# StageAudioPlayer.net
KiCad netlist of a schematic drawn in EasyEDA Pro
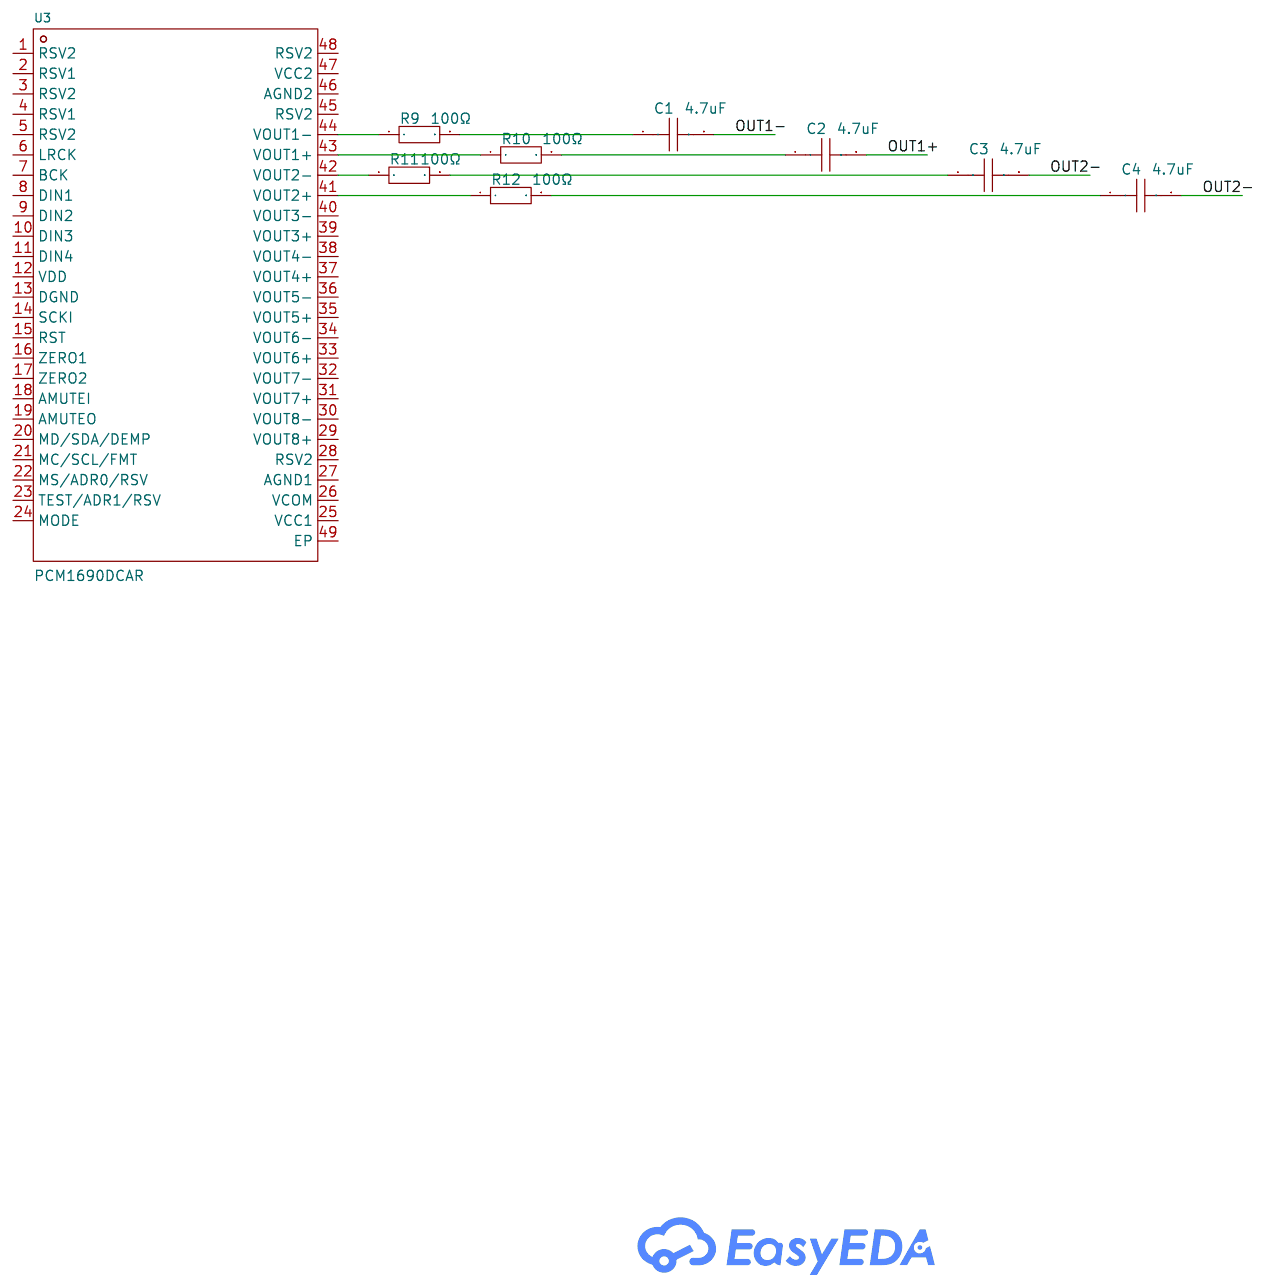
[diagram p0: schematic sheet]

(export (version "E")
  (design (tool "Eeschema 10.0.6"))
  (components
    (comp (ref "C1")
      (value "4.7uF")
      (footprint "easyedapro:CAP-TH_L28.5-W15.5-P26.0-D0.8")
      (fields (field (name "Manufacturer Part") "KP475J2J2603") (field (name "Manufacturer") "KYET(科雅)"))
      (libsource (lib "easyedapro") (part "KP475J2J2603"))
    )
    (comp (ref "C2")
      (value "4.7uF")
      (footprint "easyedapro:CAP-TH_L28.5-W15.5-P26.0-D0.8")
      (fields (field (name "Manufacturer Part") "KP475J2J2603") (field (name "Manufacturer") "KYET(科雅)"))
      (libsource (lib "easyedapro") (part "KP475J2J2603"))
    )
    (comp (ref "C3")
      (value "4.7uF")
      (footprint "easyedapro:CAP-TH_L28.5-W15.5-P26.0-D0.8")
      (fields (field (name "Manufacturer Part") "KP475J2J2603") (field (name "Manufacturer") "KYET(科雅)"))
      (libsource (lib "easyedapro") (part "KP475J2J2603"))
    )
    (comp (ref "C4")
      (value "4.7uF")
      (footprint "easyedapro:CAP-TH_L28.5-W15.5-P26.0-D0.8")
      (fields (field (name "Manufacturer Part") "KP475J2J2603") (field (name "Manufacturer") "KYET(科雅)"))
      (libsource (lib "easyedapro") (part "KP475J2J2603"))
    )
    (comp (ref "R9")
      (value "100Ω")
      (footprint "easyedapro:R0603")
      (fields
        (field (name "Manufacturer Part") "0603WAF1000T5E")
        (field (name "Manufacturer") "UNI-ROYAL(厚声)")
      )
      (libsource (lib "easyedapro") (part "0603WAF1000T5E"))
    )
    (comp (ref "R10")
      (value "100Ω")
      (footprint "easyedapro:R0603")
      (fields
        (field (name "Manufacturer Part") "0603WAF1000T5E")
        (field (name "Manufacturer") "UNI-ROYAL(厚声)")
      )
      (libsource (lib "easyedapro") (part "0603WAF1000T5E"))
    )
    (comp (ref "R11")
      (value "100Ω")
      (footprint "easyedapro:R0603")
      (fields
        (field (name "Manufacturer Part") "0603WAF1000T5E")
        (field (name "Manufacturer") "UNI-ROYAL(厚声)")
      )
      (libsource (lib "easyedapro") (part "0603WAF1000T5E"))
    )
    (comp (ref "R12")
      (value "100Ω")
      (footprint "easyedapro:R0603")
      (fields
        (field (name "Manufacturer Part") "0603WAF1000T5E")
        (field (name "Manufacturer") "UNI-ROYAL(厚声)")
      )
      (libsource (lib "easyedapro") (part "0603WAF1000T5E"))
    )
    (comp (ref "U3")
      (value "PCM1690DCAR")
      (footprint "easyedapro:HTSSOP-48_L12.5-W6.1-P0.50-LS8.1-BL-EP-1")
      (fields (field (name "Manufacturer") "TI(德州仪器)"))
      (libsource (lib "easyedapro") (part "PCM1690DCAR"))
    )
  )
  (nets
    (net (code "1") (name "/OUT1+") (class "Default")
      (node (ref "C2") (pin "2") (pinfunction "2_2") (pintype "unspecified"))
    )
    (net (code "2") (name "/OUT1-") (class "Default")
      (node (ref "C1") (pin "2") (pinfunction "2_2") (pintype "unspecified"))
    )
    (net (code "3") (name "/OUT2-") (class "Default")
      (node (ref "C3") (pin "2") (pinfunction "2_2") (pintype "unspecified"))
      (node (ref "C4") (pin "2") (pinfunction "2_2") (pintype "unspecified"))
    )
    (net (code "4") (name "Net-(C1-Pad1)") (class "Default")
      (node (ref "C1") (pin "1") (pinfunction "1_1") (pintype "unspecified"))
      (node (ref "R9") (pin "2") (pinfunction "2_2") (pintype "input"))
    )
    (net (code "5") (name "Net-(C2-Pad1)") (class "Default")
      (node (ref "C2") (pin "1") (pinfunction "1_1") (pintype "unspecified"))
      (node (ref "R10") (pin "2") (pinfunction "2_2") (pintype "input"))
    )
    (net (code "6") (name "Net-(C3-Pad1)") (class "Default")
      (node (ref "C3") (pin "1") (pinfunction "1_1") (pintype "unspecified"))
      (node (ref "R11") (pin "2") (pinfunction "2_2") (pintype "input"))
    )
    (net (code "7") (name "Net-(C4-Pad1)") (class "Default")
      (node (ref "C4") (pin "1") (pinfunction "1_1") (pintype "unspecified"))
      (node (ref "R12") (pin "2") (pinfunction "2_2") (pintype "input"))
    )
    (net (code "8") (name "Net-(U3-VOUT1+)") (class "Default")
      (node (ref "R10") (pin "1") (pinfunction "1_1") (pintype "input"))
      (node (ref "U3") (pin "43") (pinfunction "VOUT1+_43") (pintype "input"))
    )
    (net (code "9") (name "Net-(U3-VOUT1-)") (class "Default")
      (node (ref "R9") (pin "1") (pinfunction "1_1") (pintype "input"))
      (node (ref "U3") (pin "44") (pinfunction "VOUT1-_44") (pintype "input"))
    )
    (net (code "10") (name "Net-(U3-VOUT2+)") (class "Default")
      (node (ref "R12") (pin "1") (pinfunction "1_1") (pintype "input"))
      (node (ref "U3") (pin "41") (pinfunction "VOUT2+_41") (pintype "input"))
    )
    (net (code "11") (name "Net-(U3-VOUT2-)") (class "Default")
      (node (ref "R11") (pin "1") (pinfunction "1_1") (pintype "input"))
      (node (ref "U3") (pin "42") (pinfunction "VOUT2-_42") (pintype "input"))
    )
    (net (code "12") (name "unconnected-(U3-AGND1-Pad27)") (class "Default")
      (node (ref "U3") (pin "27") (pinfunction "AGND1_27") (pintype "input"))
    )
    (net (code "13") (name "unconnected-(U3-AGND2-Pad46)") (class "Default")
      (node (ref "U3") (pin "46") (pinfunction "AGND2_46") (pintype "input"))
    )
    (net (code "14") (name "unconnected-(U3-AMUTEI-Pad18)") (class "Default")
      (node (ref "U3") (pin "18") (pinfunction "AMUTEI_18") (pintype "input"))
    )
    (net (code "15") (name "unconnected-(U3-AMUTEO-Pad19)") (class "Default")
      (node (ref "U3") (pin "19") (pinfunction "AMUTEO_19") (pintype "input"))
    )
    (net (code "16") (name "unconnected-(U3-BCK-Pad7)") (class "Default")
      (node (ref "U3") (pin "7") (pinfunction "BCK_7") (pintype "input"))
    )
    (net (code "17") (name "unconnected-(U3-DGND-Pad13)") (class "Default")
      (node (ref "U3") (pin "13") (pinfunction "DGND_13") (pintype "input"))
    )
    (net (code "18") (name "unconnected-(U3-DIN1-Pad8)") (class "Default")
      (node (ref "U3") (pin "8") (pinfunction "DIN1_8") (pintype "input"))
    )
    (net (code "19") (name "unconnected-(U3-DIN2-Pad9)") (class "Default")
      (node (ref "U3") (pin "9") (pinfunction "DIN2_9") (pintype "input"))
    )
    (net (code "20") (name "unconnected-(U3-DIN3-Pad10)") (class "Default")
      (node (ref "U3") (pin "10") (pinfunction "DIN3_10") (pintype "input"))
    )
    (net (code "21") (name "unconnected-(U3-DIN4-Pad11)") (class "Default")
      (node (ref "U3") (pin "11") (pinfunction "DIN4_11") (pintype "input"))
    )
    (net (code "22") (name "unconnected-(U3-EP-Pad49)") (class "Default")
      (node (ref "U3") (pin "49") (pinfunction "EP_49") (pintype "input"))
    )
    (net (code "23") (name "unconnected-(U3-LRCK-Pad6)") (class "Default")
      (node (ref "U3") (pin "6") (pinfunction "LRCK_6") (pintype "input"))
    )
    (net (code "24") (name "unconnected-(U3-MC{slash}SCL{slash}FMT-Pad21)") (class "Default")
      (node (ref "U3") (pin "21") (pinfunction "MC/SCL/FMT_21") (pintype "input"))
    )
    (net (code "25") (name "unconnected-(U3-MD{slash}SDA{slash}DEMP-Pad20)") (class "Default")
      (node (ref "U3") (pin "20") (pinfunction "MD/SDA/DEMP_20") (pintype "input"))
    )
    (net (code "26") (name "unconnected-(U3-MODE-Pad24)") (class "Default")
      (node (ref "U3") (pin "24") (pinfunction "MODE_24") (pintype "input"))
    )
    (net (code "27") (name "unconnected-(U3-MS{slash}ADR0{slash}RSV-Pad22)") (class "Default")
      (node (ref "U3") (pin "22") (pinfunction "MS/ADR0/RSV_22") (pintype "input"))
    )
    (net (code "28") (name "unconnected-(U3-RST-Pad15)") (class "Default")
      (node (ref "U3") (pin "15") (pinfunction "RST_15") (pintype "input"))
    )
    (net (code "29") (name "unconnected-(U3-RSV1-Pad2)") (class "Default")
      (node (ref "U3") (pin "2") (pinfunction "RSV1_2") (pintype "input"))
    )
    (net (code "30") (name "unconnected-(U3-RSV1-Pad4)") (class "Default")
      (node (ref "U3") (pin "4") (pinfunction "RSV1_4") (pintype "input"))
    )
    (net (code "31") (name "unconnected-(U3-RSV2-Pad1)") (class "Default")
      (node (ref "U3") (pin "1") (pinfunction "RSV2_1") (pintype "input"))
    )
    (net (code "32") (name "unconnected-(U3-RSV2-Pad3)") (class "Default")
      (node (ref "U3") (pin "3") (pinfunction "RSV2_3") (pintype "input"))
    )
    (net (code "33") (name "unconnected-(U3-RSV2-Pad5)") (class "Default")
      (node (ref "U3") (pin "5") (pinfunction "RSV2_5") (pintype "input"))
    )
    (net (code "34") (name "unconnected-(U3-RSV2-Pad28)") (class "Default")
      (node (ref "U3") (pin "28") (pinfunction "RSV2_28") (pintype "input"))
    )
    (net (code "35") (name "unconnected-(U3-RSV2-Pad45)") (class "Default")
      (node (ref "U3") (pin "45") (pinfunction "RSV2_45") (pintype "input"))
    )
    (net (code "36") (name "unconnected-(U3-RSV2-Pad48)") (class "Default")
      (node (ref "U3") (pin "48") (pinfunction "RSV2_48") (pintype "input"))
    )
    (net (code "37") (name "unconnected-(U3-SCKI-Pad14)") (class "Default")
      (node (ref "U3") (pin "14") (pinfunction "SCKI_14") (pintype "input"))
    )
    (net (code "38") (name "unconnected-(U3-TEST{slash}ADR1{slash}RSV-Pad23)") (class "Default")
      (node (ref "U3") (pin "23") (pinfunction "TEST/ADR1/RSV_23") (pintype "input"))
    )
    (net (code "39") (name "unconnected-(U3-VCC1-Pad25)") (class "Default")
      (node (ref "U3") (pin "25") (pinfunction "VCC1_25") (pintype "input"))
    )
    (net (code "40") (name "unconnected-(U3-VCC2-Pad47)") (class "Default")
      (node (ref "U3") (pin "47") (pinfunction "VCC2_47") (pintype "input"))
    )
    (net (code "41") (name "unconnected-(U3-VCOM-Pad26)") (class "Default")
      (node (ref "U3") (pin "26") (pinfunction "VCOM_26") (pintype "input"))
    )
    (net (code "42") (name "unconnected-(U3-VDD-Pad12)") (class "Default")
      (node (ref "U3") (pin "12") (pinfunction "VDD_12") (pintype "input"))
    )
    (net (code "43") (name "unconnected-(U3-VOUT3+-Pad39)") (class "Default")
      (node (ref "U3") (pin "39") (pinfunction "VOUT3+_39") (pintype "input"))
    )
    (net (code "44") (name "unconnected-(U3-VOUT3--Pad40)") (class "Default")
      (node (ref "U3") (pin "40") (pinfunction "VOUT3-_40") (pintype "input"))
    )
    (net (code "45") (name "unconnected-(U3-VOUT4+-Pad37)") (class "Default")
      (node (ref "U3") (pin "37") (pinfunction "VOUT4+_37") (pintype "input"))
    )
    (net (code "46") (name "unconnected-(U3-VOUT4--Pad38)") (class "Default")
      (node (ref "U3") (pin "38") (pinfunction "VOUT4-_38") (pintype "input"))
    )
    (net (code "47") (name "unconnected-(U3-VOUT5+-Pad35)") (class "Default")
      (node (ref "U3") (pin "35") (pinfunction "VOUT5+_35") (pintype "input"))
    )
    (net (code "48") (name "unconnected-(U3-VOUT5--Pad36)") (class "Default")
      (node (ref "U3") (pin "36") (pinfunction "VOUT5-_36") (pintype "input"))
    )
    (net (code "49") (name "unconnected-(U3-VOUT6+-Pad33)") (class "Default")
      (node (ref "U3") (pin "33") (pinfunction "VOUT6+_33") (pintype "input"))
    )
    (net (code "50") (name "unconnected-(U3-VOUT6--Pad34)") (class "Default")
      (node (ref "U3") (pin "34") (pinfunction "VOUT6-_34") (pintype "input"))
    )
    (net (code "51") (name "unconnected-(U3-VOUT7+-Pad31)") (class "Default")
      (node (ref "U3") (pin "31") (pinfunction "VOUT7+_31") (pintype "input"))
    )
    (net (code "52") (name "unconnected-(U3-VOUT7--Pad32)") (class "Default")
      (node (ref "U3") (pin "32") (pinfunction "VOUT7-_32") (pintype "input"))
    )
    (net (code "53") (name "unconnected-(U3-VOUT8+-Pad29)") (class "Default")
      (node (ref "U3") (pin "29") (pinfunction "VOUT8+_29") (pintype "input"))
    )
    (net (code "54") (name "unconnected-(U3-VOUT8--Pad30)") (class "Default")
      (node (ref "U3") (pin "30") (pinfunction "VOUT8-_30") (pintype "input"))
    )
    (net (code "55") (name "unconnected-(U3-ZERO1-Pad16)") (class "Default")
      (node (ref "U3") (pin "16") (pinfunction "ZERO1_16") (pintype "input"))
    )
    (net (code "56") (name "unconnected-(U3-ZERO2-Pad17)") (class "Default")
      (node (ref "U3") (pin "17") (pinfunction "ZERO2_17") (pintype "input"))
    )
  )
)
